# rf_lpf.net
KiCad netlist of a schematic drawn in Altium Designer
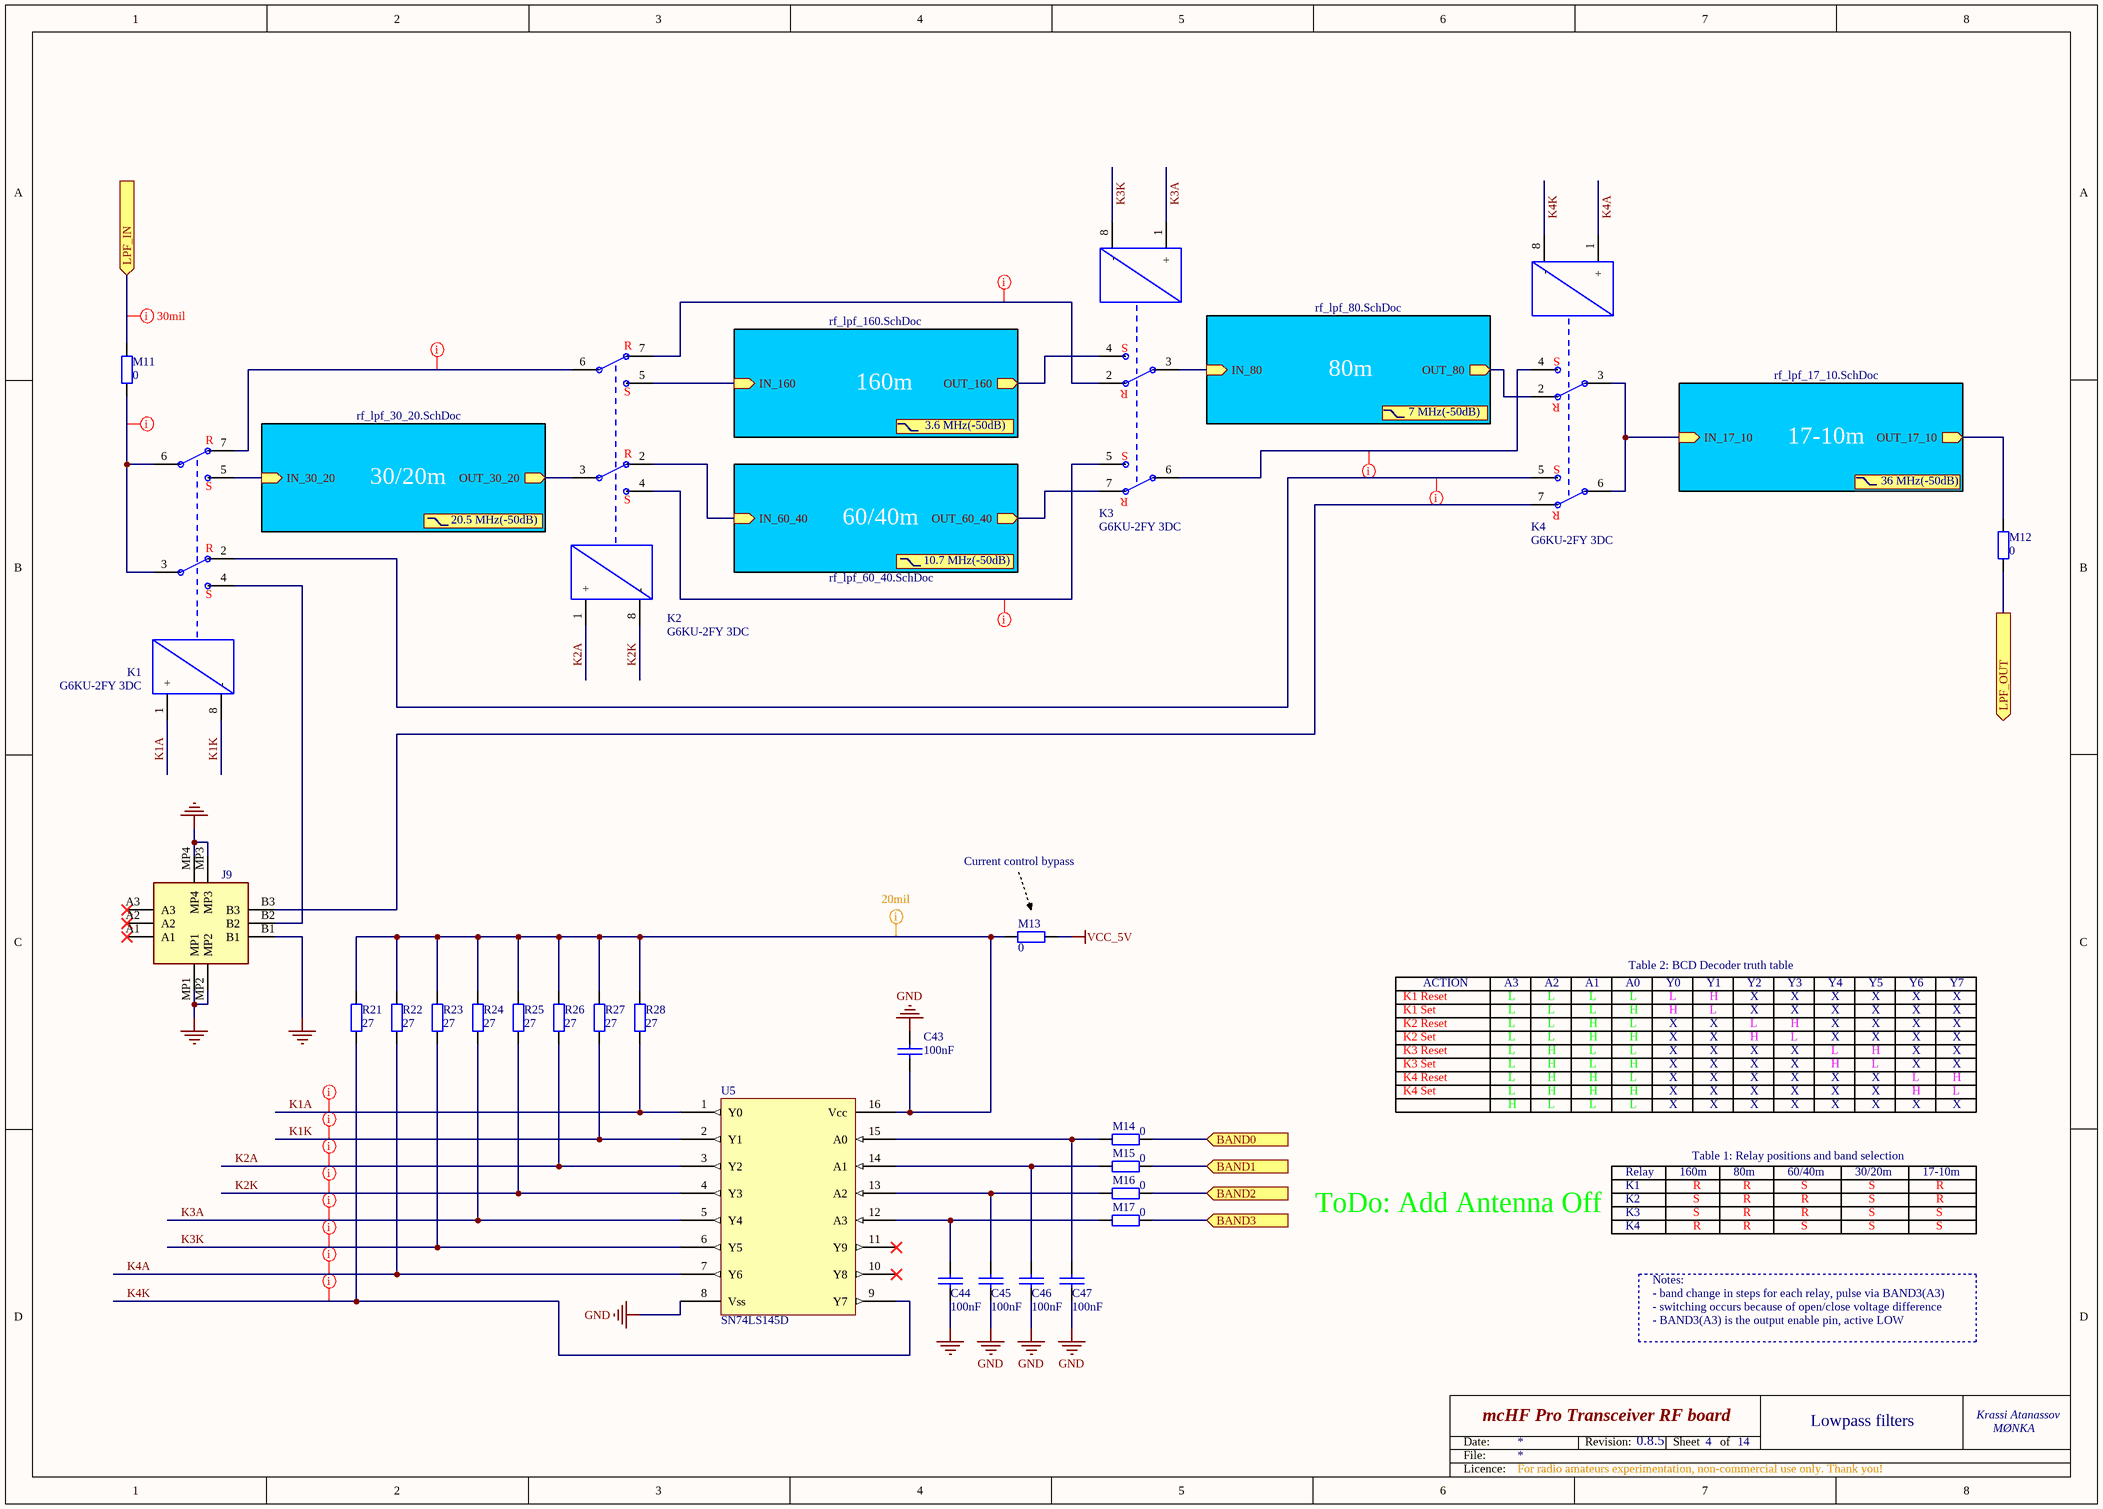
[diagram p0: rf_lpf.SchDoc]

(export (version "E")
  (design (tool "Eeschema 10.0.6"))
  (components
    (comp (ref "C43")
      (value "100nF")
      (footprint "0805")
      (description "Capacitor")
      (libsource (lib "mcHF_rf") (part "CAP"))
    )
    (comp (ref "C44")
      (value "100nF")
      (footprint "0805")
      (description "Capacitor")
      (libsource (lib "mcHF_rf") (part "CAP"))
    )
    (comp (ref "C45")
      (value "100nF")
      (footprint "0805")
      (description "Capacitor")
      (libsource (lib "mcHF_rf") (part "CAP"))
    )
    (comp (ref "C46")
      (value "100nF")
      (footprint "0805")
      (description "Capacitor")
      (libsource (lib "mcHF_rf") (part "CAP"))
    )
    (comp (ref "C47")
      (value "100nF")
      (footprint "0805")
      (description "Capacitor")
      (libsource (lib "mcHF_rf") (part "CAP"))
    )
    (comp (ref "J9")
      (value "1373826")
      (footprint "1373826")
      (fields (field (name "MOUSER PART NUMBER") "651-1373826"))
      (libsource (lib "1373826") (part "1373826"))
    )
    (comp (ref "K1")
      (value "G6KU-2FY 3DC")
      (footprint "Omron_2FY-Pro")
      (description "Single-winding Latching Relay")
      (libsource (lib "__rf") (part "G6KU-2FY 3DC"))
    )
    (comp (ref "K2")
      (value "G6KU-2FY 3DC")
      (footprint "Omron_2FY-Pro")
      (description "Single-winding Latching Relay")
      (libsource (lib "__rf") (part "G6KU-2FY 3DC"))
    )
    (comp (ref "K3")
      (value "G6KU-2FY 3DC")
      (footprint "Omron_2FY-Pro")
      (description "Single-winding Latching Relay")
      (libsource (lib "__rf") (part "G6KU-2FY 3DC"))
    )
    (comp (ref "K4")
      (value "G6KU-2FY 3DC")
      (footprint "Omron_2FY-Pro")
      (description "Single-winding Latching Relay")
      (libsource (lib "__rf") (part "G6KU-2FY 3DC"))
    )
    (comp (ref "M11")
      (value "0")
      (footprint "0805")
      (description "Resistor")
      (libsource (lib "mcHF_rf") (part "RES"))
    )
    (comp (ref "M12")
      (value "0")
      (footprint "0805")
      (description "Resistor")
      (libsource (lib "") (part "RES_3"))
    )
    (comp (ref "M13")
      (value "0")
      (footprint "0805")
      (description "Resistor")
      (libsource (lib "") (part "RES_2"))
    )
    (comp (ref "M14")
      (value "0")
      (footprint "0805")
      (description "Resistor")
      (libsource (lib "") (part "RES_1"))
    )
    (comp (ref "M15")
      (value "0")
      (footprint "0805")
      (description "Resistor")
      (libsource (lib "") (part "RES_1"))
    )
    (comp (ref "M16")
      (value "0")
      (footprint "0805")
      (description "Resistor")
      (libsource (lib "") (part "RES_1"))
    )
    (comp (ref "M17")
      (value "0")
      (footprint "0805")
      (description "Resistor")
      (libsource (lib "") (part "RES_1"))
    )
    (comp (ref "R21")
      (value "27")
      (footprint "1206")
      (description "Resistor")
      (libsource (lib "mcHF_rf") (part "RES"))
    )
    (comp (ref "R22")
      (value "27")
      (footprint "1206")
      (description "Resistor")
      (libsource (lib "mcHF_rf") (part "RES"))
    )
    (comp (ref "R23")
      (value "27")
      (footprint "1206")
      (description "Resistor")
      (libsource (lib "mcHF_rf") (part "RES"))
    )
    (comp (ref "R24")
      (value "27")
      (footprint "1206")
      (description "Resistor")
      (libsource (lib "mcHF_rf") (part "RES"))
    )
    (comp (ref "R25")
      (value "27")
      (footprint "1206")
      (description "Resistor")
      (libsource (lib "mcHF_rf") (part "RES"))
    )
    (comp (ref "R26")
      (value "27")
      (footprint "1206")
      (description "Resistor")
      (libsource (lib "mcHF_rf") (part "RES"))
    )
    (comp (ref "R27")
      (value "27")
      (footprint "1206")
      (description "Resistor")
      (libsource (lib "mcHF_rf") (part "RES"))
    )
    (comp (ref "R28")
      (value "27")
      (footprint "1206")
      (description "Resistor")
      (libsource (lib "mcHF_rf") (part "RES"))
    )
    (comp (ref "U5")
      (value "SN74LS145D")
      (footprint "SO-16")
      (description "BCD DECODER/DRIVER")
      (libsource (lib "mcHF_rf") (part "SN74LS145D"))
    )
  )
  (nets
    (net (code "1") (name "/BAND0") (class "Default")
      (node (ref "M14") (pin "1") (pinfunction "1_1") (pintype "passive"))
    )
    (net (code "2") (name "/BAND1") (class "Default")
      (node (ref "M15") (pin "1") (pinfunction "1_1") (pintype "passive"))
    )
    (net (code "3") (name "/BAND2") (class "Default")
      (node (ref "M16") (pin "1") (pinfunction "1_1") (pintype "passive"))
    )
    (net (code "4") (name "/BAND3") (class "Default")
      (node (ref "M17") (pin "1") (pinfunction "1_1") (pintype "passive"))
    )
    (net (code "5") (name "/IN_17_10") (class "Default")
      (node (ref "K4") (pin "3") (pinfunction "3_3") (pintype "passive"))
      (node (ref "K4") (pin "6") (pinfunction "6_6") (pintype "passive"))
    )
    (net (code "6") (name "/IN_30_20") (class "Default")
      (node (ref "K1") (pin "5") (pinfunction "5_5") (pintype "passive"))
    )
    (net (code "7") (name "/IN_60_40") (class "Default")
      (node (ref "K2") (pin "2") (pinfunction "2_2") (pintype "passive"))
    )
    (net (code "8") (name "/IN_80") (class "Default")
      (node (ref "K3") (pin "3") (pinfunction "3_3") (pintype "passive"))
    )
    (net (code "9") (name "/IN_160") (class "Default")
      (node (ref "K2") (pin "5") (pinfunction "5_5") (pintype "passive"))
    )
    (net (code "10") (name "/K1A") (class "Default")
      (node (ref "K1") (pin "1") (pinfunction "+_1") (pintype "passive"))
      (node (ref "R28") (pin "1") (pinfunction "1_1") (pintype "passive"))
      (node (ref "U5") (pin "1") (pinfunction "Y0_1") (pintype "output"))
    )
    (net (code "11") (name "/K1K") (class "Default")
      (node (ref "K1") (pin "8") (pinfunction "-_8") (pintype "passive"))
      (node (ref "R27") (pin "1") (pinfunction "1_1") (pintype "passive"))
      (node (ref "U5") (pin "2") (pinfunction "Y1_2") (pintype "output"))
    )
    (net (code "12") (name "/K2A") (class "Default")
      (node (ref "K2") (pin "1") (pinfunction "+_1") (pintype "passive"))
      (node (ref "R26") (pin "1") (pinfunction "1_1") (pintype "passive"))
      (node (ref "U5") (pin "3") (pinfunction "Y2_3") (pintype "output"))
    )
    (net (code "13") (name "/K2K") (class "Default")
      (node (ref "K2") (pin "8") (pinfunction "-_8") (pintype "passive"))
      (node (ref "R25") (pin "1") (pinfunction "1_1") (pintype "passive"))
      (node (ref "U5") (pin "4") (pinfunction "Y3_4") (pintype "output"))
    )
    (net (code "14") (name "/K3A") (class "Default")
      (node (ref "K3") (pin "1") (pinfunction "+_1") (pintype "passive"))
      (node (ref "R24") (pin "1") (pinfunction "1_1") (pintype "passive"))
      (node (ref "U5") (pin "5") (pinfunction "Y4_5") (pintype "output"))
    )
    (net (code "15") (name "/K3K") (class "Default")
      (node (ref "K3") (pin "8") (pinfunction "-_8") (pintype "passive"))
      (node (ref "R23") (pin "1") (pinfunction "1_1") (pintype "passive"))
      (node (ref "U5") (pin "6") (pinfunction "Y5_6") (pintype "output"))
    )
    (net (code "16") (name "/K4A") (class "Default")
      (node (ref "K4") (pin "1") (pinfunction "+_1") (pintype "passive"))
      (node (ref "R22") (pin "1") (pinfunction "1_1") (pintype "passive"))
      (node (ref "U5") (pin "7") (pinfunction "Y6_7") (pintype "output"))
    )
    (net (code "17") (name "/K4K") (class "Default")
      (node (ref "K4") (pin "8") (pinfunction "-_8") (pintype "passive"))
      (node (ref "R21") (pin "1") (pinfunction "1_1") (pintype "passive"))
      (node (ref "U5") (pin "9") (pinfunction "Y7_9") (pintype "output"))
    )
    (net (code "18") (name "/LPF_IN") (class "Default")
      (node (ref "M11") (pin "2") (pinfunction "2_2") (pintype "passive"))
    )
    (net (code "19") (name "/LPF_OUT") (class "Default")
      (node (ref "M12") (pin "2") (pinfunction "2_2") (pintype "passive"))
    )
    (net (code "20") (name "/OUT_17_10") (class "Default")
      (node (ref "M12") (pin "1") (pinfunction "1_1") (pintype "passive"))
    )
    (net (code "21") (name "/OUT_30_20") (class "Default")
      (node (ref "K2") (pin "3") (pinfunction "3_3") (pintype "passive"))
    )
    (net (code "22") (name "/OUT_60_40") (class "Default")
      (node (ref "K3") (pin "7") (pinfunction "7_7") (pintype "passive"))
    )
    (net (code "23") (name "/OUT_80") (class "Default")
      (node (ref "K4") (pin "2") (pinfunction "2_2") (pintype "passive"))
    )
    (net (code "24") (name "/OUT_160") (class "Default")
      (node (ref "K3") (pin "4") (pinfunction "4_4") (pintype "passive"))
    )
    (net (code "25") (name "GND") (class "Default")
      (node (ref "C43") (pin "2") (pinfunction "2_2") (pintype "passive"))
      (node (ref "C44") (pin "1") (pinfunction "1_1") (pintype "passive"))
      (node (ref "C45") (pin "1") (pinfunction "1_1") (pintype "passive"))
      (node (ref "C46") (pin "1") (pinfunction "1_1") (pintype "passive"))
      (node (ref "C47") (pin "1") (pinfunction "1_1") (pintype "passive"))
      (node (ref "J9") (pin "B1") (pinfunction "B1_B1") (pintype "passive"))
      (node (ref "J9") (pin "MP1") (pinfunction "MP1_MP1") (pintype "passive"))
      (node (ref "J9") (pin "MP2") (pinfunction "MP2_MP2") (pintype "passive"))
      (node (ref "J9") (pin "MP3") (pinfunction "MP3_MP3") (pintype "passive"))
      (node (ref "J9") (pin "MP4") (pinfunction "MP4_MP4") (pintype "passive"))
      (node (ref "U5") (pin "8") (pinfunction "Vss_8") (pintype "power_in"))
    )
    (net (code "26") (name "Net-(J9-PadB2)") (class "Default")
      (node (ref "J9") (pin "B2") (pinfunction "B2_B2") (pintype "passive"))
      (node (ref "K1") (pin "4") (pinfunction "4_4") (pintype "passive"))
    )
    (net (code "27") (name "Net-(J9-PadB3)") (class "Default")
      (node (ref "J9") (pin "B3") (pinfunction "B3_B3") (pintype "passive"))
      (node (ref "K4") (pin "7") (pinfunction "7_7") (pintype "passive"))
    )
    (net (code "28") (name "Net-(K1-Pad2)") (class "Default")
      (node (ref "K1") (pin "2") (pinfunction "2_2") (pintype "passive"))
      (node (ref "K4") (pin "5") (pinfunction "5_5") (pintype "passive"))
    )
    (net (code "29") (name "Net-(K1-Pad3)") (class "Default")
      (node (ref "K1") (pin "3") (pinfunction "3_3") (pintype "passive"))
      (node (ref "K1") (pin "6") (pinfunction "6_6") (pintype "passive"))
      (node (ref "M11") (pin "1") (pinfunction "1_1") (pintype "passive"))
    )
    (net (code "30") (name "Net-(K1-Pad7)") (class "Default")
      (node (ref "K1") (pin "7") (pinfunction "7_7") (pintype "passive"))
      (node (ref "K2") (pin "6") (pinfunction "6_6") (pintype "passive"))
    )
    (net (code "31") (name "Net-(K2-Pad4)") (class "Default")
      (node (ref "K2") (pin "4") (pinfunction "4_4") (pintype "passive"))
      (node (ref "K3") (pin "5") (pinfunction "5_5") (pintype "passive"))
    )
    (net (code "32") (name "Net-(K2-Pad7)") (class "Default")
      (node (ref "K2") (pin "7") (pinfunction "7_7") (pintype "passive"))
      (node (ref "K3") (pin "2") (pinfunction "2_2") (pintype "passive"))
    )
    (net (code "33") (name "Net-(K3-Pad6)") (class "Default")
      (node (ref "K3") (pin "6") (pinfunction "6_6") (pintype "passive"))
      (node (ref "K4") (pin "4") (pinfunction "4_4") (pintype "passive"))
    )
    (net (code "34") (name "Net-(U5-A0)") (class "Default")
      (node (ref "C47") (pin "2") (pinfunction "2_2") (pintype "passive"))
      (node (ref "M14") (pin "2") (pinfunction "2_2") (pintype "passive"))
      (node (ref "U5") (pin "15") (pinfunction "A0_15") (pintype "input"))
    )
    (net (code "35") (name "Net-(U5-A1)") (class "Default")
      (node (ref "C46") (pin "2") (pinfunction "2_2") (pintype "passive"))
      (node (ref "M15") (pin "2") (pinfunction "2_2") (pintype "passive"))
      (node (ref "U5") (pin "14") (pinfunction "A1_14") (pintype "input"))
    )
    (net (code "36") (name "Net-(U5-A2)") (class "Default")
      (node (ref "C45") (pin "2") (pinfunction "2_2") (pintype "passive"))
      (node (ref "M16") (pin "2") (pinfunction "2_2") (pintype "passive"))
      (node (ref "U5") (pin "13") (pinfunction "A2_13") (pintype "input"))
    )
    (net (code "37") (name "Net-(U5-A3)") (class "Default")
      (node (ref "C44") (pin "2") (pinfunction "2_2") (pintype "passive"))
      (node (ref "M17") (pin "2") (pinfunction "2_2") (pintype "passive"))
      (node (ref "U5") (pin "12") (pinfunction "A3_12") (pintype "input"))
    )
    (net (code "38") (name "Net-(U5-Vcc)") (class "Default")
      (node (ref "C43") (pin "1") (pinfunction "1_1") (pintype "passive"))
      (node (ref "M13") (pin "1") (pinfunction "1_1") (pintype "passive"))
      (node (ref "R21") (pin "2") (pinfunction "2_2") (pintype "passive"))
      (node (ref "R22") (pin "2") (pinfunction "2_2") (pintype "passive"))
      (node (ref "R23") (pin "2") (pinfunction "2_2") (pintype "passive"))
      (node (ref "R24") (pin "2") (pinfunction "2_2") (pintype "passive"))
      (node (ref "R25") (pin "2") (pinfunction "2_2") (pintype "passive"))
      (node (ref "R26") (pin "2") (pinfunction "2_2") (pintype "passive"))
      (node (ref "R27") (pin "2") (pinfunction "2_2") (pintype "passive"))
      (node (ref "R28") (pin "2") (pinfunction "2_2") (pintype "passive"))
      (node (ref "U5") (pin "16") (pinfunction "Vcc_16") (pintype "power_in"))
    )
    (net (code "39") (name "VCC_5V") (class "Default")
      (node (ref "M13") (pin "2") (pinfunction "2_2") (pintype "passive"))
    )
    (net (code "40") (name "unconnected-(J9-PadA1)") (class "Default")
      (node (ref "J9") (pin "A1") (pinfunction "A1_A1") (pintype "passive+no_connect"))
    )
    (net (code "41") (name "unconnected-(J9-PadA2)") (class "Default")
      (node (ref "J9") (pin "A2") (pinfunction "A2_A2") (pintype "passive+no_connect"))
    )
    (net (code "42") (name "unconnected-(J9-PadA3)") (class "Default")
      (node (ref "J9") (pin "A3") (pinfunction "A3_A3") (pintype "passive+no_connect"))
    )
    (net (code "43") (name "unconnected-(U5-Y8-Pad10)") (class "Default")
      (node (ref "U5") (pin "10") (pinfunction "Y8_10") (pintype "output+no_connect"))
    )
    (net (code "44") (name "unconnected-(U5-Y9-Pad11)") (class "Default")
      (node (ref "U5") (pin "11") (pinfunction "Y9_11") (pintype "output+no_connect"))
    )
  )
)
